# Beeclust_MicroMouse_v1_0.net
KiCad netlist of a schematic drawn in EAGLE
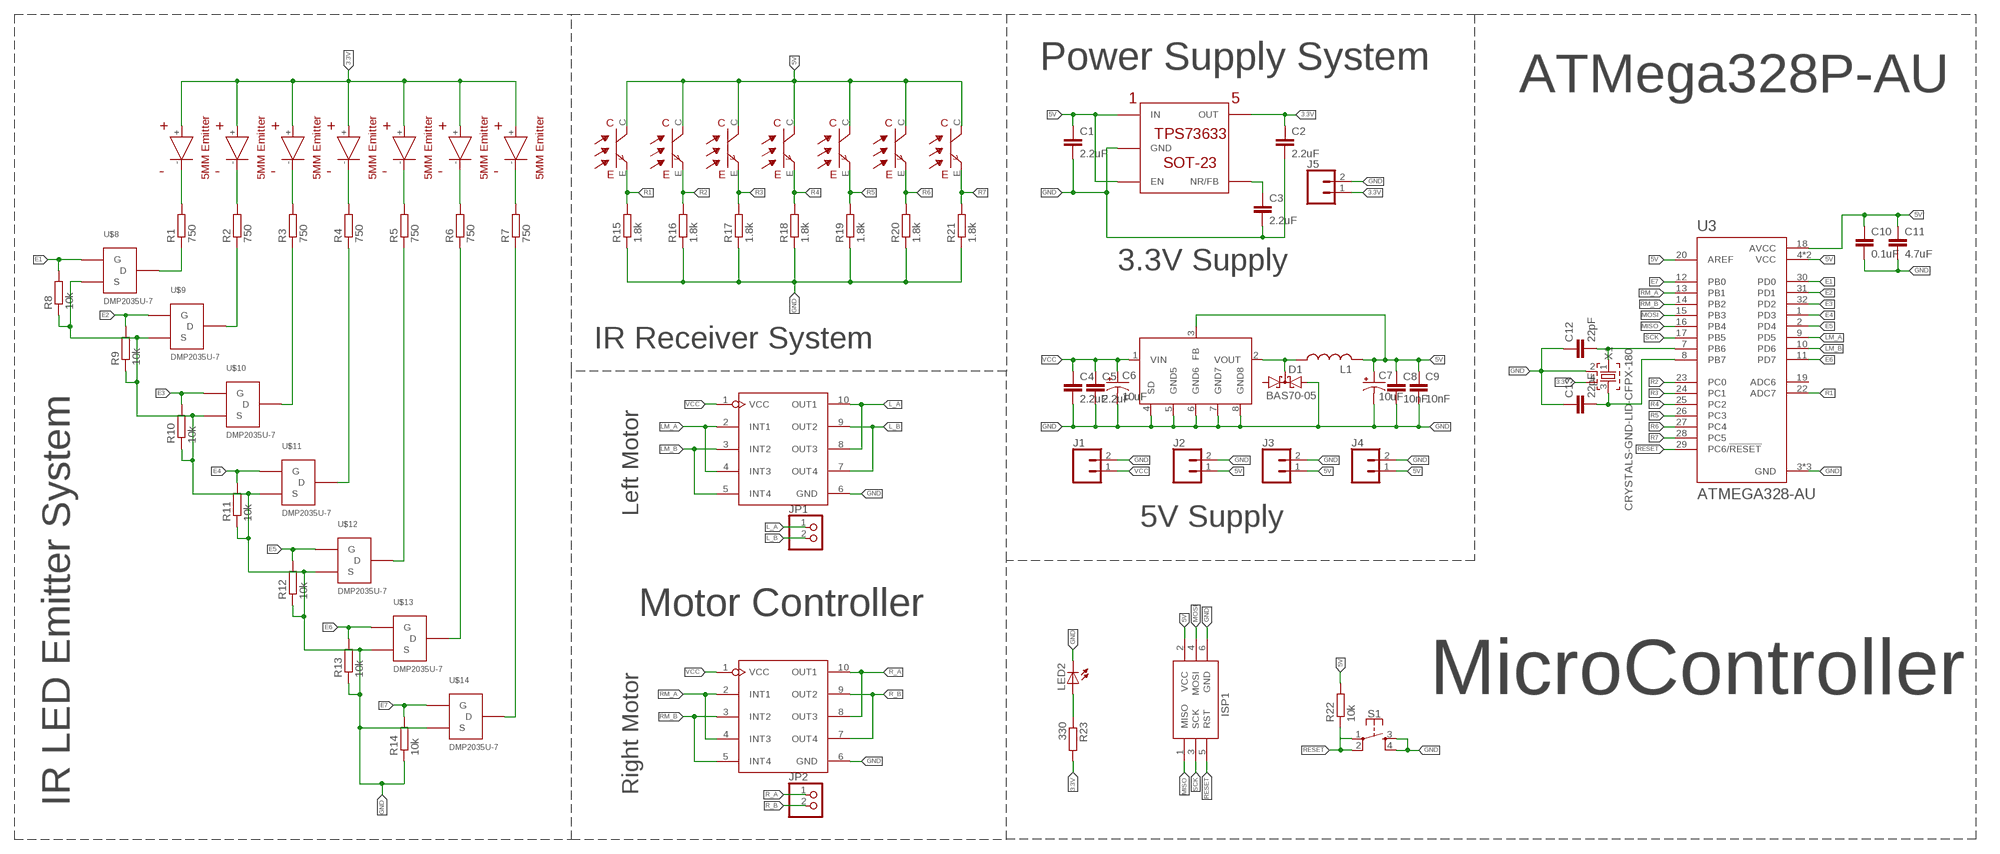
[diagram p0: schematic, sheet 1, part 1 of 2]
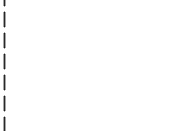
[diagram p1: schematic, sheet 1, part 2 of 2]

(export (version "E")
  (design (tool "Eeschema 10.0.6"))
  (components
    (comp (ref "C1")
      (value "2.2uF")
      (footprint "eagle-import:0603")
      (libsource (lib "eagle-import") (part "2.2UF-0603-10V-20%"))
    )
    (comp (ref "C2")
      (value "2.2uF")
      (footprint "eagle-import:0603")
      (libsource (lib "eagle-import") (part "2.2UF-0603-10V-20%"))
    )
    (comp (ref "C3")
      (value "2.2uF")
      (footprint "eagle-import:0603")
      (libsource (lib "eagle-import") (part "2.2UF-0603-10V-20%"))
    )
    (comp (ref "C4")
      (value "2.2uF")
      (footprint "eagle-import:0603")
      (libsource (lib "eagle-import") (part "2.2UF-0603-10V-20%"))
    )
    (comp (ref "C5")
      (value "2.2uF")
      (footprint "eagle-import:0603")
      (libsource (lib "eagle-import") (part "2.2UF-0603-10V-20%"))
    )
    (comp (ref "C6")
      (value "10uF")
      (footprint "eagle-import:0603-POLAR")
      (libsource (lib "eagle-import") (part "10UF-POLAR-0603-6.3V-20%(TANT)"))
    )
    (comp (ref "C7")
      (value "10uF")
      (footprint "eagle-import:0603-POLAR")
      (libsource (lib "eagle-import") (part "10UF-POLAR-0603-6.3V-20%(TANT)"))
    )
    (comp (ref "C8")
      (value "10nF")
      (footprint "eagle-import:0603")
      (libsource (lib "eagle-import") (part "10NF-0603-50V-10%"))
    )
    (comp (ref "C9")
      (value "10nF")
      (footprint "eagle-import:0603")
      (libsource (lib "eagle-import") (part "10NF-0603-50V-10%"))
    )
    (comp (ref "C10")
      (value "0.1uF")
      (footprint "eagle-import:0603")
      (libsource (lib "eagle-import") (part "0.1UF-0603-25V-(+80/-20%)"))
    )
    (comp (ref "C11")
      (value "4.7uF")
      (footprint "eagle-import:0603")
      (libsource (lib "eagle-import") (part "4.7UF0603"))
    )
    (comp (ref "C12")
      (value "22pF")
      (footprint "eagle-import:0603")
      (libsource (lib "eagle-import") (part "22PF-0603-50V-5%"))
    )
    (comp (ref "C13")
      (value "22pF")
      (footprint "eagle-import:0603")
      (libsource (lib "eagle-import") (part "22PF-0603-50V-5%"))
    )
    (comp (ref "D1")
      (value "BAS70-05")
      (footprint "eagle-import:SOT23")
      (libsource (lib "eagle-import") (part "BAS70-05"))
    )
    (comp (ref "ISP1")
      (value "AVRISP-6")
      (footprint "eagle-import:AVRISP")
      (libsource (lib "eagle-import") (part "AVRISP-6"))
    )
    (comp (ref "J1")
      (value "CONN_02PTH3")
      (footprint "eagle-import:1X02_LONGPADS")
      (libsource (lib "eagle-import") (part "CONN_02PTH3"))
    )
    (comp (ref "J2")
      (value "CONN_02PTH3")
      (footprint "eagle-import:1X02_LONGPADS")
      (libsource (lib "eagle-import") (part "CONN_02PTH3"))
    )
    (comp (ref "J3")
      (value "CONN_02PTH3")
      (footprint "eagle-import:1X02_LONGPADS")
      (libsource (lib "eagle-import") (part "CONN_02PTH3"))
    )
    (comp (ref "J4")
      (value "CONN_02PTH3")
      (footprint "eagle-import:1X02_LONGPADS")
      (libsource (lib "eagle-import") (part "CONN_02PTH3"))
    )
    (comp (ref "J5")
      (value "CONN_02PTH3")
      (footprint "eagle-import:1X02_LONGPADS")
      (libsource (lib "eagle-import") (part "CONN_02PTH3"))
    )
    (comp (ref "JP1")
      (value "PINHD-1X2")
      (footprint "eagle-import:1X02")
      (libsource (lib "eagle-import") (part "PINHD-1X2"))
    )
    (comp (ref "JP2")
      (value "PINHD-1X2")
      (footprint "eagle-import:1X02")
      (libsource (lib "eagle-import") (part "PINHD-1X2"))
    )
    (comp (ref "L1")
      (value "L-USL0201")
      (footprint "eagle-import:L0201")
      (libsource (lib "eagle-import") (part "L-USL0201"))
    )
    (comp (ref "LED2")
      (value "LEDCHIP-LED0603")
      (footprint "eagle-import:CHIP-LED0603")
      (libsource (lib "eagle-import") (part "LEDCHIP-LED0603"))
    )
    (comp (ref "R1")
      (value "750")
      (footprint "eagle-import:R0603")
      (libsource (lib "eagle-import") (part "R-EU_R0603"))
    )
    (comp (ref "R2")
      (value "750")
      (footprint "eagle-import:R0603")
      (libsource (lib "eagle-import") (part "R-EU_R0603"))
    )
    (comp (ref "R3")
      (value "750")
      (footprint "eagle-import:R0603")
      (libsource (lib "eagle-import") (part "R-EU_R0603"))
    )
    (comp (ref "R4")
      (value "750")
      (footprint "eagle-import:R0603")
      (libsource (lib "eagle-import") (part "R-EU_R0603"))
    )
    (comp (ref "R5")
      (value "750")
      (footprint "eagle-import:R0603")
      (libsource (lib "eagle-import") (part "R-EU_R0603"))
    )
    (comp (ref "R6")
      (value "750")
      (footprint "eagle-import:R0603")
      (libsource (lib "eagle-import") (part "R-EU_R0603"))
    )
    (comp (ref "R7")
      (value "750")
      (footprint "eagle-import:R0603")
      (libsource (lib "eagle-import") (part "R-EU_R0603"))
    )
    (comp (ref "R8")
      (value "10k")
      (footprint "eagle-import:R0603")
      (libsource (lib "eagle-import") (part "R-EU_R0603"))
    )
    (comp (ref "R9")
      (value "10k")
      (footprint "eagle-import:R0603")
      (libsource (lib "eagle-import") (part "R-EU_R0603"))
    )
    (comp (ref "R10")
      (value "10k")
      (footprint "eagle-import:R0603")
      (libsource (lib "eagle-import") (part "R-EU_R0603"))
    )
    (comp (ref "R11")
      (value "10k")
      (footprint "eagle-import:R0603")
      (libsource (lib "eagle-import") (part "R-EU_R0603"))
    )
    (comp (ref "R12")
      (value "10k")
      (footprint "eagle-import:R0603")
      (libsource (lib "eagle-import") (part "R-EU_R0603"))
    )
    (comp (ref "R13")
      (value "10k")
      (footprint "eagle-import:R0603")
      (libsource (lib "eagle-import") (part "R-EU_R0603"))
    )
    (comp (ref "R14")
      (value "10k")
      (footprint "eagle-import:R0603")
      (libsource (lib "eagle-import") (part "R-EU_R0603"))
    )
    (comp (ref "R15")
      (value "1.8k")
      (footprint "eagle-import:R0603")
      (libsource (lib "eagle-import") (part "R-EU_R0603"))
    )
    (comp (ref "R16")
      (value "1.8k")
      (footprint "eagle-import:R0603")
      (libsource (lib "eagle-import") (part "R-EU_R0603"))
    )
    (comp (ref "R17")
      (value "1.8k")
      (footprint "eagle-import:R0603")
      (libsource (lib "eagle-import") (part "R-EU_R0603"))
    )
    (comp (ref "R18")
      (value "1.8k")
      (footprint "eagle-import:R0603")
      (libsource (lib "eagle-import") (part "R-EU_R0603"))
    )
    (comp (ref "R19")
      (value "1.8k")
      (footprint "eagle-import:R0603")
      (libsource (lib "eagle-import") (part "R-EU_R0603"))
    )
    (comp (ref "R20")
      (value "1.8k")
      (footprint "eagle-import:R0603")
      (libsource (lib "eagle-import") (part "R-EU_R0603"))
    )
    (comp (ref "R21")
      (value "1.8k")
      (footprint "eagle-import:R0603")
      (libsource (lib "eagle-import") (part "R-EU_R0603"))
    )
    (comp (ref "R22")
      (value "10k")
      (footprint "eagle-import:R0603")
      (libsource (lib "eagle-import") (part "R-EU_R0603"))
    )
    (comp (ref "R23")
      (value "330")
      (footprint "eagle-import:R0603")
      (libsource (lib "eagle-import") (part "R-EU_R0603"))
    )
    (comp (ref "S1")
      (value "MOMENTARY-SWITCH-SPST-2-SMD-5.2MM")
      (footprint "eagle-import:TACTILE_SWITCH_SMD_5.2MM")
      (libsource (lib "eagle-import") (part "MOMENTARY-SWITCH-SPST-2-SMD-5.2MM"))
    )
    (comp (ref "U$1")
      (value "EMITTER")
      (footprint "eagle-import:EMITTER")
      (libsource (lib "eagle-import") (part "EMITTER"))
    )
    (comp (ref "U$2")
      (value "EMITTER")
      (footprint "eagle-import:EMITTER")
      (libsource (lib "eagle-import") (part "EMITTER"))
    )
    (comp (ref "U$3")
      (value "EMITTER")
      (footprint "eagle-import:EMITTER")
      (libsource (lib "eagle-import") (part "EMITTER"))
    )
    (comp (ref "U$4")
      (value "EMITTER")
      (footprint "eagle-import:EMITTER")
      (libsource (lib "eagle-import") (part "EMITTER"))
    )
    (comp (ref "U$5")
      (value "EMITTER")
      (footprint "eagle-import:EMITTER")
      (libsource (lib "eagle-import") (part "EMITTER"))
    )
    (comp (ref "U$6")
      (value "EMITTER")
      (footprint "eagle-import:EMITTER")
      (libsource (lib "eagle-import") (part "EMITTER"))
    )
    (comp (ref "U$7")
      (value "EMITTER")
      (footprint "eagle-import:EMITTER")
      (libsource (lib "eagle-import") (part "EMITTER"))
    )
    (comp (ref "U$8")
      (value "DMP2035U-7")
      (footprint "eagle-import:SOT23")
      (fields (field (name "MF") "Diodes Inc."))
      (libsource (lib "eagle-import") (part "DMP2035U-7"))
    )
    (comp (ref "U$9")
      (value "DMP2035U-7")
      (footprint "eagle-import:SOT23")
      (fields (field (name "MF") "Diodes Inc."))
      (libsource (lib "eagle-import") (part "DMP2035U-7"))
    )
    (comp (ref "U$10")
      (value "DMP2035U-7")
      (footprint "eagle-import:SOT23")
      (fields (field (name "MF") "Diodes Inc."))
      (libsource (lib "eagle-import") (part "DMP2035U-7"))
    )
    (comp (ref "U$11")
      (value "DMP2035U-7")
      (footprint "eagle-import:SOT23")
      (fields (field (name "MF") "Diodes Inc."))
      (libsource (lib "eagle-import") (part "DMP2035U-7"))
    )
    (comp (ref "U$12")
      (value "DMP2035U-7")
      (footprint "eagle-import:SOT23")
      (fields (field (name "MF") "Diodes Inc."))
      (libsource (lib "eagle-import") (part "DMP2035U-7"))
    )
    (comp (ref "U$13")
      (value "DMP2035U-7")
      (footprint "eagle-import:SOT23")
      (fields (field (name "MF") "Diodes Inc."))
      (libsource (lib "eagle-import") (part "DMP2035U-7"))
    )
    (comp (ref "U$14")
      (value "DMP2035U-7")
      (footprint "eagle-import:SOT23")
      (fields (field (name "MF") "Diodes Inc."))
      (libsource (lib "eagle-import") (part "DMP2035U-7"))
    )
    (comp (ref "U$15")
      (value "RECEIVER")
      (footprint "eagle-import:RECEIVER")
      (libsource (lib "eagle-import") (part "RECEIVER"))
    )
    (comp (ref "U$16")
      (value "RECEIVER")
      (footprint "eagle-import:RECEIVER")
      (libsource (lib "eagle-import") (part "RECEIVER"))
    )
    (comp (ref "U$17")
      (value "RECEIVER")
      (footprint "eagle-import:RECEIVER")
      (libsource (lib "eagle-import") (part "RECEIVER"))
    )
    (comp (ref "U$18")
      (value "RECEIVER")
      (footprint "eagle-import:RECEIVER")
      (libsource (lib "eagle-import") (part "RECEIVER"))
    )
    (comp (ref "U$19")
      (value "RECEIVER")
      (footprint "eagle-import:RECEIVER")
      (libsource (lib "eagle-import") (part "RECEIVER"))
    )
    (comp (ref "U$20")
      (value "RECEIVER")
      (footprint "eagle-import:RECEIVER")
      (libsource (lib "eagle-import") (part "RECEIVER"))
    )
    (comp (ref "U$21")
      (value "RECEIVER")
      (footprint "eagle-import:RECEIVER")
      (libsource (lib "eagle-import") (part "RECEIVER"))
    )
    (comp (ref "U$22")
      (value "TPS73633(SOT-23)")
      (footprint "eagle-import:TPS73633(SOT-23)")
      (libsource (lib "eagle-import") (part "TPS73633(SOT-23)"))
    )
    (comp (ref "U$23")
      (value "AP1509-50SG-13")
      (footprint "eagle-import:SO08")
      (fields (field (name "MF") "Diodes Inc."))
      (libsource (lib "eagle-import") (part "AP1509-50SG-13"))
    )
    (comp (ref "U1")
      (value "DRIVER-LV8548MC-AH(SOIC10)")
      (footprint "eagle-import:SOIC10-1.0-5X4MM")
      (fields (field (name "MF") "ON Semiconductor") (field (name "MP") "LV8548MC-AH"))
      (libsource (lib "eagle-import") (part "DRIVER-LV8548MC-AH(SOIC10)"))
    )
    (comp (ref "U2")
      (value "DRIVER-LV8548MC-AH(SOIC10)")
      (footprint "eagle-import:SOIC10-1.0-5X4MM")
      (fields (field (name "MF") "ON Semiconductor") (field (name "MP") "LV8548MC-AH"))
      (libsource (lib "eagle-import") (part "DRIVER-LV8548MC-AH(SOIC10)"))
    )
    (comp (ref "U3")
      (value "ATMEGA328-AU")
      (footprint "eagle-import:QFP80P900X900X120-32N")
      (fields (field (name "MF") "Microchip"))
      (libsource (lib "eagle-import") (part "ATMEGA328-AU"))
    )
    (comp (ref "X1")
      (value "CRYSTALS-GND-LID-CFPX-180")
      (footprint "eagle-import:3.4X2.7-4-PAD")
      (libsource (lib "eagle-import") (part "CRYSTALS-GND-LID-CFPX-180"))
    )
  )
  (nets
    (net (code "1") (name "3.3V") (class "Default")
      (node (ref "C2") (pin "1") (pinfunction "1_1") (pintype "passive"))
      (node (ref "J5") (pin "1") (pinfunction "1_1") (pintype "passive"))
      (node (ref "R23") (pin "2") (pinfunction "2_2") (pintype "passive"))
      (node (ref "U$1") (pin "+") (pinfunction "+_+") (pintype "bidirectional"))
      (node (ref "U$2") (pin "+") (pinfunction "+_+") (pintype "bidirectional"))
      (node (ref "U$22") (pin "OUT") (pinfunction "OUT_OUT") (pintype "bidirectional"))
      (node (ref "U$3") (pin "+") (pinfunction "+_+") (pintype "bidirectional"))
      (node (ref "U$4") (pin "+") (pinfunction "+_+") (pintype "bidirectional"))
      (node (ref "U$5") (pin "+") (pinfunction "+_+") (pintype "bidirectional"))
      (node (ref "U$6") (pin "+") (pinfunction "+_+") (pintype "bidirectional"))
      (node (ref "U$7") (pin "+") (pinfunction "+_+") (pintype "bidirectional"))
      (node (ref "X1") (pin "4") (pinfunction "4_4") (pintype "passive"))
    )
    (net (code "2") (name "5V") (class "Default")
      (node (ref "C1") (pin "1") (pinfunction "1_1") (pintype "passive"))
      (node (ref "C10") (pin "1") (pinfunction "1_1") (pintype "passive"))
      (node (ref "C11") (pin "1") (pinfunction "1_1") (pintype "passive"))
      (node (ref "C7") (pin "+") (pinfunction "+_+") (pintype "passive"))
      (node (ref "C8") (pin "1") (pinfunction "1_1") (pintype "passive"))
      (node (ref "C9") (pin "1") (pinfunction "1_1") (pintype "passive"))
      (node (ref "ISP1") (pin "2") (pinfunction "VCC_2") (pintype "power_in"))
      (node (ref "J2") (pin "1") (pinfunction "1_1") (pintype "passive"))
      (node (ref "J3") (pin "1") (pinfunction "1_1") (pintype "passive"))
      (node (ref "J4") (pin "1") (pinfunction "1_1") (pintype "passive"))
      (node (ref "L1") (pin "2") (pinfunction "2_2") (pintype "passive"))
      (node (ref "R22") (pin "2") (pinfunction "2_2") (pintype "passive"))
      (node (ref "U$15") (pin "C") (pinfunction "C_C") (pintype "bidirectional"))
      (node (ref "U$16") (pin "C") (pinfunction "C_C") (pintype "bidirectional"))
      (node (ref "U$17") (pin "C") (pinfunction "C_C") (pintype "bidirectional"))
      (node (ref "U$18") (pin "C") (pinfunction "C_C") (pintype "bidirectional"))
      (node (ref "U$19") (pin "C") (pinfunction "C_C") (pintype "bidirectional"))
      (node (ref "U$20") (pin "C") (pinfunction "C_C") (pintype "bidirectional"))
      (node (ref "U$21") (pin "C") (pinfunction "C_C") (pintype "bidirectional"))
      (node (ref "U$22") (pin "EN") (pinfunction "EN_EN") (pintype "bidirectional"))
      (node (ref "U$22") (pin "IN") (pinfunction "IN_IN") (pintype "bidirectional"))
      (node (ref "U$23") (pin "3") (pinfunction "FB_3") (pintype "bidirectional"))
      (node (ref "U3") (pin "18") (pinfunction "AVCC_18") (pintype "power_in"))
      (node (ref "U3") (pin "20") (pinfunction "AREF_20") (pintype "input"))
      (node (ref "U3") (pin "4") (pinfunction "VCC_4") (pintype "power_in"))
      (node (ref "U3") (pin "6") (pinfunction "VCC_6") (pintype "power_in"))
    )
    (net (code "3") (name "E1") (class "Default")
      (node (ref "R8") (pin "2") (pinfunction "2_2") (pintype "passive"))
      (node (ref "U$8") (pin "1") (pinfunction "G_1") (pintype "bidirectional"))
      (node (ref "U3") (pin "30") (pinfunction "PD0_30") (pintype "bidirectional"))
    )
    (net (code "4") (name "E2") (class "Default")
      (node (ref "R9") (pin "2") (pinfunction "2_2") (pintype "passive"))
      (node (ref "U$9") (pin "1") (pinfunction "G_1") (pintype "bidirectional"))
      (node (ref "U3") (pin "31") (pinfunction "PD1_31") (pintype "bidirectional"))
    )
    (net (code "5") (name "E3") (class "Default")
      (node (ref "R10") (pin "2") (pinfunction "2_2") (pintype "passive"))
      (node (ref "U$10") (pin "1") (pinfunction "G_1") (pintype "bidirectional"))
      (node (ref "U3") (pin "32") (pinfunction "PD2_32") (pintype "bidirectional"))
    )
    (net (code "6") (name "E4") (class "Default")
      (node (ref "R11") (pin "2") (pinfunction "2_2") (pintype "passive"))
      (node (ref "U$11") (pin "1") (pinfunction "G_1") (pintype "bidirectional"))
      (node (ref "U3") (pin "1") (pinfunction "PD3_1") (pintype "bidirectional"))
    )
    (net (code "7") (name "E5") (class "Default")
      (node (ref "R12") (pin "2") (pinfunction "2_2") (pintype "passive"))
      (node (ref "U$12") (pin "1") (pinfunction "G_1") (pintype "bidirectional"))
      (node (ref "U3") (pin "2") (pinfunction "PD4_2") (pintype "bidirectional"))
    )
    (net (code "8") (name "E6") (class "Default")
      (node (ref "R13") (pin "2") (pinfunction "2_2") (pintype "passive"))
      (node (ref "U$13") (pin "1") (pinfunction "G_1") (pintype "bidirectional"))
      (node (ref "U3") (pin "11") (pinfunction "PD7_11") (pintype "bidirectional"))
    )
    (net (code "9") (name "E7") (class "Default")
      (node (ref "R14") (pin "2") (pinfunction "2_2") (pintype "passive"))
      (node (ref "U$14") (pin "1") (pinfunction "G_1") (pintype "bidirectional"))
      (node (ref "U3") (pin "12") (pinfunction "PB0_12") (pintype "bidirectional"))
    )
    (net (code "10") (name "GND") (class "Default")
      (node (ref "C1") (pin "2") (pinfunction "2_2") (pintype "passive"))
      (node (ref "C10") (pin "2") (pinfunction "2_2") (pintype "passive"))
      (node (ref "C11") (pin "2") (pinfunction "2_2") (pintype "passive"))
      (node (ref "C12") (pin "1") (pinfunction "1_1") (pintype "passive"))
      (node (ref "C13") (pin "1") (pinfunction "1_1") (pintype "passive"))
      (node (ref "C2") (pin "2") (pinfunction "2_2") (pintype "passive"))
      (node (ref "C3") (pin "2") (pinfunction "2_2") (pintype "passive"))
      (node (ref "C4") (pin "2") (pinfunction "2_2") (pintype "passive"))
      (node (ref "C5") (pin "2") (pinfunction "2_2") (pintype "passive"))
      (node (ref "C6") (pin "-") (pinfunction "-_-") (pintype "passive"))
      (node (ref "C7") (pin "-") (pinfunction "-_-") (pintype "passive"))
      (node (ref "C8") (pin "2") (pinfunction "2_2") (pintype "passive"))
      (node (ref "C9") (pin "2") (pinfunction "2_2") (pintype "passive"))
      (node (ref "D1") (pin "2") (pinfunction "A2_2") (pintype "passive"))
      (node (ref "ISP1") (pin "6") (pinfunction "GND_6") (pintype "power_in"))
      (node (ref "J1") (pin "2") (pinfunction "2_2") (pintype "passive"))
      (node (ref "J2") (pin "2") (pinfunction "2_2") (pintype "passive"))
      (node (ref "J3") (pin "2") (pinfunction "2_2") (pintype "passive"))
      (node (ref "J4") (pin "2") (pinfunction "2_2") (pintype "passive"))
      (node (ref "J5") (pin "2") (pinfunction "2_2") (pintype "passive"))
      (node (ref "LED2") (pin "C") (pinfunction "C_C") (pintype "passive"))
      (node (ref "R10") (pin "1") (pinfunction "1_1") (pintype "passive"))
      (node (ref "R11") (pin "1") (pinfunction "1_1") (pintype "passive"))
      (node (ref "R12") (pin "1") (pinfunction "1_1") (pintype "passive"))
      (node (ref "R13") (pin "1") (pinfunction "1_1") (pintype "passive"))
      (node (ref "R14") (pin "1") (pinfunction "1_1") (pintype "passive"))
      (node (ref "R15") (pin "1") (pinfunction "1_1") (pintype "passive"))
      (node (ref "R16") (pin "1") (pinfunction "1_1") (pintype "passive"))
      (node (ref "R17") (pin "1") (pinfunction "1_1") (pintype "passive"))
      (node (ref "R18") (pin "1") (pinfunction "1_1") (pintype "passive"))
      (node (ref "R19") (pin "1") (pinfunction "1_1") (pintype "passive"))
      (node (ref "R20") (pin "1") (pinfunction "1_1") (pintype "passive"))
      (node (ref "R21") (pin "1") (pinfunction "1_1") (pintype "passive"))
      (node (ref "R8") (pin "1") (pinfunction "1_1") (pintype "passive"))
      (node (ref "R9") (pin "1") (pinfunction "1_1") (pintype "passive"))
      (node (ref "S1") (pin "3") (pinfunction "3_3") (pintype "passive"))
      (node (ref "S1") (pin "4") (pinfunction "4_4") (pintype "passive"))
      (node (ref "U$10") (pin "2") (pinfunction "S_2") (pintype "bidirectional"))
      (node (ref "U$11") (pin "2") (pinfunction "S_2") (pintype "bidirectional"))
      (node (ref "U$12") (pin "2") (pinfunction "S_2") (pintype "bidirectional"))
      (node (ref "U$13") (pin "2") (pinfunction "S_2") (pintype "bidirectional"))
      (node (ref "U$14") (pin "2") (pinfunction "S_2") (pintype "bidirectional"))
      (node (ref "U$22") (pin "GND") (pinfunction "GND_GND") (pintype "bidirectional"))
      (node (ref "U$23") (pin "4") (pinfunction "SD_4") (pintype "bidirectional"))
      (node (ref "U$23") (pin "5") (pinfunction "GND5_5") (pintype "bidirectional"))
      (node (ref "U$23") (pin "6") (pinfunction "GND6_6") (pintype "bidirectional"))
      (node (ref "U$23") (pin "7") (pinfunction "GND7_7") (pintype "bidirectional"))
      (node (ref "U$23") (pin "8") (pinfunction "GND8_8") (pintype "bidirectional"))
      (node (ref "U$8") (pin "2") (pinfunction "S_2") (pintype "bidirectional"))
      (node (ref "U$9") (pin "2") (pinfunction "S_2") (pintype "bidirectional"))
      (node (ref "U1") (pin "6") (pinfunction "GND_6") (pintype "bidirectional"))
      (node (ref "U2") (pin "6") (pinfunction "GND_6") (pintype "bidirectional"))
      (node (ref "U3") (pin "21") (pinfunction "GND_21") (pintype "power_in"))
      (node (ref "U3") (pin "3") (pinfunction "GND_3") (pintype "power_in"))
      (node (ref "U3") (pin "5") (pinfunction "GND_5") (pintype "power_in"))
      (node (ref "X1") (pin "2") (pinfunction "2_2") (pintype "passive"))
    )
    (net (code "11") (name "LM_A") (class "Default")
      (node (ref "U1") (pin "2") (pinfunction "INT1_2") (pintype "bidirectional"))
      (node (ref "U1") (pin "4") (pinfunction "INT3_4") (pintype "bidirectional"))
      (node (ref "U3") (pin "9") (pinfunction "PD5_9") (pintype "bidirectional"))
    )
    (net (code "12") (name "LM_B") (class "Default")
      (node (ref "U1") (pin "3") (pinfunction "INT2_3") (pintype "bidirectional"))
      (node (ref "U1") (pin "5") (pinfunction "INT4_5") (pintype "bidirectional"))
      (node (ref "U3") (pin "10") (pinfunction "PD6_10") (pintype "bidirectional"))
    )
    (net (code "13") (name "L_A") (class "Default")
      (node (ref "JP1") (pin "1") (pinfunction "1_1") (pintype "passive"))
      (node (ref "U1") (pin "10") (pinfunction "OUT1_10") (pintype "bidirectional"))
      (node (ref "U1") (pin "8") (pinfunction "OUT3_8") (pintype "bidirectional"))
    )
    (net (code "14") (name "L_B") (class "Default")
      (node (ref "JP1") (pin "2") (pinfunction "2_2") (pintype "passive"))
      (node (ref "U1") (pin "7") (pinfunction "OUT4_7") (pintype "bidirectional"))
      (node (ref "U1") (pin "9") (pinfunction "OUT2_9") (pintype "bidirectional"))
    )
    (net (code "15") (name "MISO") (class "Default")
      (node (ref "ISP1") (pin "1") (pinfunction "MISO_1") (pintype "input"))
      (node (ref "U3") (pin "16") (pinfunction "PB4_16") (pintype "bidirectional"))
    )
    (net (code "16") (name "MOSI") (class "Default")
      (node (ref "ISP1") (pin "4") (pinfunction "MOSI_4") (pintype "output"))
      (node (ref "U3") (pin "15") (pinfunction "PB3_15") (pintype "bidirectional"))
    )
    (net (code "17") (name "Net-(C3-Pad1)") (class "Default")
      (node (ref "C3") (pin "1") (pinfunction "1_1") (pintype "passive"))
      (node (ref "U$22") (pin "NR/FB") (pinfunction "NR/FB_NR/FB") (pintype "bidirectional"))
    )
    (net (code "18") (name "Net-(D1-C)") (class "Default")
      (node (ref "D1") (pin "3") (pinfunction "C_3") (pintype "passive"))
      (node (ref "L1") (pin "1") (pinfunction "1_1") (pintype "passive"))
      (node (ref "U$23") (pin "2") (pinfunction "VOUT_2") (pintype "bidirectional"))
    )
    (net (code "19") (name "Net-(LED2-PadA)") (class "Default")
      (node (ref "LED2") (pin "A") (pinfunction "A_A") (pintype "passive"))
      (node (ref "R23") (pin "1") (pinfunction "1_1") (pintype "passive"))
    )
    (net (code "20") (name "Net-(R1-Pad2)") (class "Default")
      (node (ref "R1") (pin "2") (pinfunction "2_2") (pintype "passive"))
      (node (ref "U$1") (pin "-") (pinfunction "-_-") (pintype "bidirectional"))
    )
    (net (code "21") (name "Net-(R2-Pad2)") (class "Default")
      (node (ref "R2") (pin "2") (pinfunction "2_2") (pintype "passive"))
      (node (ref "U$2") (pin "-") (pinfunction "-_-") (pintype "bidirectional"))
    )
    (net (code "22") (name "Net-(R3-Pad2)") (class "Default")
      (node (ref "R3") (pin "2") (pinfunction "2_2") (pintype "passive"))
      (node (ref "U$3") (pin "-") (pinfunction "-_-") (pintype "bidirectional"))
    )
    (net (code "23") (name "Net-(R4-Pad2)") (class "Default")
      (node (ref "R4") (pin "2") (pinfunction "2_2") (pintype "passive"))
      (node (ref "U$4") (pin "-") (pinfunction "-_-") (pintype "bidirectional"))
    )
    (net (code "24") (name "Net-(R5-Pad2)") (class "Default")
      (node (ref "R5") (pin "2") (pinfunction "2_2") (pintype "passive"))
      (node (ref "U$5") (pin "-") (pinfunction "-_-") (pintype "bidirectional"))
    )
    (net (code "25") (name "Net-(R6-Pad2)") (class "Default")
      (node (ref "R6") (pin "2") (pinfunction "2_2") (pintype "passive"))
      (node (ref "U$6") (pin "-") (pinfunction "-_-") (pintype "bidirectional"))
    )
    (net (code "26") (name "Net-(R7-Pad2)") (class "Default")
      (node (ref "R7") (pin "2") (pinfunction "2_2") (pintype "passive"))
      (node (ref "U$7") (pin "-") (pinfunction "-_-") (pintype "bidirectional"))
    )
    (net (code "27") (name "Net-(U$8-D)") (class "Default")
      (node (ref "R1") (pin "1") (pinfunction "1_1") (pintype "passive"))
      (node (ref "U$8") (pin "3") (pinfunction "D_3") (pintype "bidirectional"))
    )
    (net (code "28") (name "Net-(U$9-D)") (class "Default")
      (node (ref "R2") (pin "1") (pinfunction "1_1") (pintype "passive"))
      (node (ref "U$9") (pin "3") (pinfunction "D_3") (pintype "bidirectional"))
    )
    (net (code "29") (name "Net-(U$10-D)") (class "Default")
      (node (ref "R3") (pin "1") (pinfunction "1_1") (pintype "passive"))
      (node (ref "U$10") (pin "3") (pinfunction "D_3") (pintype "bidirectional"))
    )
    (net (code "30") (name "Net-(U$11-D)") (class "Default")
      (node (ref "R4") (pin "1") (pinfunction "1_1") (pintype "passive"))
      (node (ref "U$11") (pin "3") (pinfunction "D_3") (pintype "bidirectional"))
    )
    (net (code "31") (name "Net-(U$12-D)") (class "Default")
      (node (ref "R5") (pin "1") (pinfunction "1_1") (pintype "passive"))
      (node (ref "U$12") (pin "3") (pinfunction "D_3") (pintype "bidirectional"))
    )
    (net (code "32") (name "Net-(U$13-D)") (class "Default")
      (node (ref "R6") (pin "1") (pinfunction "1_1") (pintype "passive"))
      (node (ref "U$13") (pin "3") (pinfunction "D_3") (pintype "bidirectional"))
    )
    (net (code "33") (name "Net-(U$14-D)") (class "Default")
      (node (ref "R7") (pin "1") (pinfunction "1_1") (pintype "passive"))
      (node (ref "U$14") (pin "3") (pinfunction "D_3") (pintype "bidirectional"))
    )
    (net (code "34") (name "Net-(U3-PB6)") (class "Default")
      (node (ref "C12") (pin "2") (pinfunction "2_2") (pintype "passive"))
      (node (ref "U3") (pin "7") (pinfunction "PB6_7") (pintype "bidirectional"))
      (node (ref "X1") (pin "1") (pinfunction "1_1") (pintype "passive"))
    )
    (net (code "35") (name "Net-(U3-PB7)") (class "Default")
      (node (ref "C13") (pin "2") (pinfunction "2_2") (pintype "passive"))
      (node (ref "U3") (pin "8") (pinfunction "PB7_8") (pintype "bidirectional"))
      (node (ref "X1") (pin "3") (pinfunction "3_3") (pintype "passive"))
    )
    (net (code "36") (name "R1") (class "Default")
      (node (ref "R15") (pin "2") (pinfunction "2_2") (pintype "passive"))
      (node (ref "U$15") (pin "E") (pinfunction "E_E") (pintype "bidirectional"))
      (node (ref "U3") (pin "22") (pinfunction "ADC7_22") (pintype "bidirectional"))
    )
    (net (code "37") (name "R2") (class "Default")
      (node (ref "R16") (pin "2") (pinfunction "2_2") (pintype "passive"))
      (node (ref "U$16") (pin "E") (pinfunction "E_E") (pintype "bidirectional"))
      (node (ref "U3") (pin "23") (pinfunction "PC0_23") (pintype "bidirectional"))
    )
    (net (code "38") (name "R3") (class "Default")
      (node (ref "R17") (pin "2") (pinfunction "2_2") (pintype "passive"))
      (node (ref "U$17") (pin "E") (pinfunction "E_E") (pintype "bidirectional"))
      (node (ref "U3") (pin "24") (pinfunction "PC1_24") (pintype "bidirectional"))
    )
    (net (code "39") (name "R4") (class "Default")
      (node (ref "R18") (pin "2") (pinfunction "2_2") (pintype "passive"))
      (node (ref "U$18") (pin "E") (pinfunction "E_E") (pintype "bidirectional"))
      (node (ref "U3") (pin "25") (pinfunction "PC2_25") (pintype "bidirectional"))
    )
    (net (code "40") (name "R5") (class "Default")
      (node (ref "R19") (pin "2") (pinfunction "2_2") (pintype "passive"))
      (node (ref "U$19") (pin "E") (pinfunction "E_E") (pintype "bidirectional"))
      (node (ref "U3") (pin "26") (pinfunction "PC3_26") (pintype "bidirectional"))
    )
    (net (code "41") (name "R6") (class "Default")
      (node (ref "R20") (pin "2") (pinfunction "2_2") (pintype "passive"))
      (node (ref "U$20") (pin "E") (pinfunction "E_E") (pintype "bidirectional"))
      (node (ref "U3") (pin "27") (pinfunction "PC4_27") (pintype "bidirectional"))
    )
    (net (code "42") (name "R7") (class "Default")
      (node (ref "R21") (pin "2") (pinfunction "2_2") (pintype "passive"))
      (node (ref "U$21") (pin "E") (pinfunction "E_E") (pintype "bidirectional"))
      (node (ref "U3") (pin "28") (pinfunction "PC5_28") (pintype "bidirectional"))
    )
    (net (code "43") (name "RESET") (class "Default")
      (node (ref "ISP1") (pin "5") (pinfunction "RST_5") (pintype "output"))
      (node (ref "R22") (pin "1") (pinfunction "1_1") (pintype "passive"))
      (node (ref "S1") (pin "1") (pinfunction "1_1") (pintype "passive"))
      (node (ref "S1") (pin "2") (pinfunction "2_2") (pintype "passive"))
      (node (ref "U3") (pin "29") (pinfunction "PC6/~{RESET}_29") (pintype "bidirectional"))
    )
    (net (code "44") (name "RM_A") (class "Default")
      (node (ref "U2") (pin "2") (pinfunction "INT1_2") (pintype "bidirectional"))
      (node (ref "U2") (pin "4") (pinfunction "INT3_4") (pintype "bidirectional"))
      (node (ref "U3") (pin "13") (pinfunction "PB1_13") (pintype "bidirectional"))
    )
    (net (code "45") (name "RM_B") (class "Default")
      (node (ref "U2") (pin "3") (pinfunction "INT2_3") (pintype "bidirectional"))
      (node (ref "U2") (pin "5") (pinfunction "INT4_5") (pintype "bidirectional"))
      (node (ref "U3") (pin "14") (pinfunction "PB2_14") (pintype "bidirectional"))
    )
    (net (code "46") (name "R_A") (class "Default")
      (node (ref "JP2") (pin "1") (pinfunction "1_1") (pintype "passive"))
      (node (ref "U2") (pin "10") (pinfunction "OUT1_10") (pintype "bidirectional"))
      (node (ref "U2") (pin "8") (pinfunction "OUT3_8") (pintype "bidirectional"))
    )
    (net (code "47") (name "R_B") (class "Default")
      (node (ref "JP2") (pin "2") (pinfunction "2_2") (pintype "passive"))
      (node (ref "U2") (pin "7") (pinfunction "OUT4_7") (pintype "bidirectional"))
      (node (ref "U2") (pin "9") (pinfunction "OUT2_9") (pintype "bidirectional"))
    )
    (net (code "48") (name "SCK") (class "Default")
      (node (ref "ISP1") (pin "3") (pinfunction "SCK_3") (pintype "output"))
      (node (ref "U3") (pin "17") (pinfunction "PB5_17") (pintype "bidirectional"))
    )
    (net (code "49") (name "VCC") (class "Default")
      (node (ref "C4") (pin "1") (pinfunction "1_1") (pintype "passive"))
      (node (ref "C5") (pin "1") (pinfunction "1_1") (pintype "passive"))
      (node (ref "C6") (pin "+") (pinfunction "+_+") (pintype "passive"))
      (node (ref "J1") (pin "1") (pinfunction "1_1") (pintype "passive"))
      (node (ref "U$23") (pin "1") (pinfunction "VIN_1") (pintype "bidirectional"))
      (node (ref "U1") (pin "1") (pinfunction "VCC_1") (pintype "bidirectional"))
      (node (ref "U2") (pin "1") (pinfunction "VCC_1") (pintype "bidirectional"))
    )
    (net (code "50") (name "unconnected-(D1-A1-Pad1)") (class "Default")
      (node (ref "D1") (pin "1") (pinfunction "A1_1") (pintype "passive"))
    )
    (net (code "51") (name "unconnected-(U3-ADC6-Pad19)") (class "Default")
      (node (ref "U3") (pin "19") (pinfunction "ADC6_19") (pintype "bidirectional"))
    )
  )
)
